# BrakeLightNM.net
KiCad netlist of a schematic drawn in Altium Designer
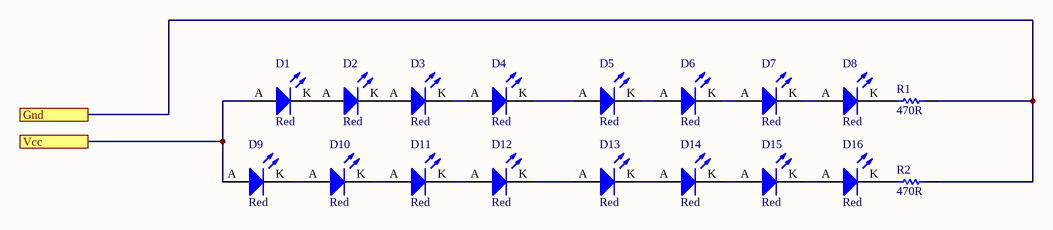
[diagram p0: BrakeLightNM.SchDoc]

(export (version "E")
  (design (tool "Eeschema 10.0.6"))
  (components
    (comp (ref "D1")
      (value "Red")
      (footprint "0805 LED")
      (description "Red LED Indication - Discrete 1.75V 0805 (2012 Metric)")
      (fields (field (name "PART NUMBER") "SML-210LTT86") (field (name "MANUFACTURER") "ROHM Semiconductor"))
      (libsource (lib "ts_20-standard-library") (part "LED"))
    )
    (comp (ref "D2")
      (value "Red")
      (footprint "0805 LED")
      (description "Red LED Indication - Discrete 1.75V 0805 (2012 Metric)")
      (fields (field (name "PART NUMBER") "SML-210LTT86") (field (name "MANUFACTURER") "ROHM Semiconductor"))
      (libsource (lib "ts_20-standard-library") (part "LED"))
    )
    (comp (ref "D3")
      (value "Red")
      (footprint "0805 LED")
      (description "Red LED Indication - Discrete 1.75V 0805 (2012 Metric)")
      (fields (field (name "PART NUMBER") "SML-210LTT86") (field (name "MANUFACTURER") "ROHM Semiconductor"))
      (libsource (lib "ts_20-standard-library") (part "LED"))
    )
    (comp (ref "D4")
      (value "Red")
      (footprint "0805 LED")
      (description "Red LED Indication - Discrete 1.75V 0805 (2012 Metric)")
      (fields (field (name "PART NUMBER") "SML-210LTT86") (field (name "MANUFACTURER") "ROHM Semiconductor"))
      (libsource (lib "ts_20-standard-library") (part "LED"))
    )
    (comp (ref "D5")
      (value "Red")
      (footprint "0805 LED")
      (description "Red LED Indication - Discrete 1.75V 0805 (2012 Metric)")
      (fields (field (name "PART NUMBER") "SML-210LTT86") (field (name "MANUFACTURER") "ROHM Semiconductor"))
      (libsource (lib "ts_20-standard-library") (part "LED"))
    )
    (comp (ref "D6")
      (value "Red")
      (footprint "0805 LED")
      (description "Red LED Indication - Discrete 1.75V 0805 (2012 Metric)")
      (fields (field (name "PART NUMBER") "SML-210LTT86") (field (name "MANUFACTURER") "ROHM Semiconductor"))
      (libsource (lib "ts_20-standard-library") (part "LED"))
    )
    (comp (ref "D7")
      (value "Red")
      (footprint "0805 LED")
      (description "Red LED Indication - Discrete 1.75V 0805 (2012 Metric)")
      (fields (field (name "PART NUMBER") "SML-210LTT86") (field (name "MANUFACTURER") "ROHM Semiconductor"))
      (libsource (lib "ts_20-standard-library") (part "LED"))
    )
    (comp (ref "D8")
      (value "Red")
      (footprint "0805 LED")
      (description "Red LED Indication - Discrete 1.75V 0805 (2012 Metric)")
      (fields (field (name "PART NUMBER") "SML-210LTT86") (field (name "MANUFACTURER") "ROHM Semiconductor"))
      (libsource (lib "ts_20-standard-library") (part "LED"))
    )
    (comp (ref "D9")
      (value "Red")
      (footprint "0805 LED")
      (description "Red LED Indication - Discrete 1.75V 0805 (2012 Metric)")
      (fields (field (name "PART NUMBER") "SML-210LTT86") (field (name "MANUFACTURER") "ROHM Semiconductor"))
      (libsource (lib "ts_20-standard-library") (part "LED"))
    )
    (comp (ref "D10")
      (value "Red")
      (footprint "0805 LED")
      (description "Red LED Indication - Discrete 1.75V 0805 (2012 Metric)")
      (fields (field (name "PART NUMBER") "SML-210LTT86") (field (name "MANUFACTURER") "ROHM Semiconductor"))
      (libsource (lib "ts_20-standard-library") (part "LED"))
    )
    (comp (ref "D11")
      (value "Red")
      (footprint "0805 LED")
      (description "Red LED Indication - Discrete 1.75V 0805 (2012 Metric)")
      (fields (field (name "PART NUMBER") "SML-210LTT86") (field (name "MANUFACTURER") "ROHM Semiconductor"))
      (libsource (lib "ts_20-standard-library") (part "LED"))
    )
    (comp (ref "D12")
      (value "Red")
      (footprint "0805 LED")
      (description "Red LED Indication - Discrete 1.75V 0805 (2012 Metric)")
      (fields (field (name "PART NUMBER") "SML-210LTT86") (field (name "MANUFACTURER") "ROHM Semiconductor"))
      (libsource (lib "ts_20-standard-library") (part "LED"))
    )
    (comp (ref "D13")
      (value "Red")
      (footprint "0805 LED")
      (description "Red LED Indication - Discrete 1.75V 0805 (2012 Metric)")
      (fields (field (name "PART NUMBER") "SML-210LTT86") (field (name "MANUFACTURER") "ROHM Semiconductor"))
      (libsource (lib "ts_20-standard-library") (part "LED"))
    )
    (comp (ref "D14")
      (value "Red")
      (footprint "0805 LED")
      (description "Red LED Indication - Discrete 1.75V 0805 (2012 Metric)")
      (fields (field (name "PART NUMBER") "SML-210LTT86") (field (name "MANUFACTURER") "ROHM Semiconductor"))
      (libsource (lib "ts_20-standard-library") (part "LED"))
    )
    (comp (ref "D15")
      (value "Red")
      (footprint "0805 LED")
      (description "Red LED Indication - Discrete 1.75V 0805 (2012 Metric)")
      (fields (field (name "PART NUMBER") "SML-210LTT86") (field (name "MANUFACTURER") "ROHM Semiconductor"))
      (libsource (lib "ts_20-standard-library") (part "LED"))
    )
    (comp (ref "D16")
      (value "Red")
      (footprint "0805 LED")
      (description "Red LED Indication - Discrete 1.75V 0805 (2012 Metric)")
      (fields (field (name "PART NUMBER") "SML-210LTT86") (field (name "MANUFACTURER") "ROHM Semiconductor"))
      (libsource (lib "ts_20-standard-library") (part "LED"))
    )
    (comp (ref "R1")
      (value "470R")
      (footprint "0805")
      (fields
        (field (name "PART NUMBER") "RC0805FR07470RL")
        (field (name "MANUFACTURER") "YAGEO")
        (field (name "TOLERANCE") "0.01")
      )
      (libsource (lib "ts_20-standard-library") (part "Resistor"))
    )
    (comp (ref "R2")
      (value "470R")
      (footprint "0805")
      (fields
        (field (name "PART NUMBER") "RC0805FR07470RL")
        (field (name "MANUFACTURER") "YAGEO")
        (field (name "TOLERANCE") "0.01")
      )
      (libsource (lib "ts_20-standard-library") (part "Resistor"))
    )
  )
  (nets
    (net (code "1") (name "/Gnd") (class "Default")
      (node (ref "R1") (pin "2") (pinfunction "2_2") (pintype "passive"))
      (node (ref "R2") (pin "2") (pinfunction "2_2") (pintype "passive"))
    )
    (net (code "2") (name "/Vcc") (class "Default")
      (node (ref "D1") (pin "A") (pinfunction "A_A") (pintype "passive"))
      (node (ref "D9") (pin "A") (pinfunction "A_A") (pintype "passive"))
    )
    (net (code "3") (name "Net-(D1-PadK)") (class "Default")
      (node (ref "D1") (pin "K") (pinfunction "K_K") (pintype "passive"))
      (node (ref "D2") (pin "A") (pinfunction "A_A") (pintype "passive"))
    )
    (net (code "4") (name "Net-(D2-PadK)") (class "Default")
      (node (ref "D2") (pin "K") (pinfunction "K_K") (pintype "passive"))
      (node (ref "D3") (pin "A") (pinfunction "A_A") (pintype "passive"))
    )
    (net (code "5") (name "Net-(D3-PadK)") (class "Default")
      (node (ref "D3") (pin "K") (pinfunction "K_K") (pintype "passive"))
      (node (ref "D4") (pin "A") (pinfunction "A_A") (pintype "passive"))
    )
    (net (code "6") (name "Net-(D4-PadK)") (class "Default")
      (node (ref "D4") (pin "K") (pinfunction "K_K") (pintype "passive"))
      (node (ref "D5") (pin "A") (pinfunction "A_A") (pintype "passive"))
    )
    (net (code "7") (name "Net-(D5-PadK)") (class "Default")
      (node (ref "D5") (pin "K") (pinfunction "K_K") (pintype "passive"))
      (node (ref "D6") (pin "A") (pinfunction "A_A") (pintype "passive"))
    )
    (net (code "8") (name "Net-(D6-PadK)") (class "Default")
      (node (ref "D6") (pin "K") (pinfunction "K_K") (pintype "passive"))
      (node (ref "D7") (pin "A") (pinfunction "A_A") (pintype "passive"))
    )
    (net (code "9") (name "Net-(D7-PadK)") (class "Default")
      (node (ref "D7") (pin "K") (pinfunction "K_K") (pintype "passive"))
      (node (ref "D8") (pin "A") (pinfunction "A_A") (pintype "passive"))
    )
    (net (code "10") (name "Net-(D8-PadK)") (class "Default")
      (node (ref "D8") (pin "K") (pinfunction "K_K") (pintype "passive"))
      (node (ref "R1") (pin "1") (pinfunction "1_1") (pintype "passive"))
    )
    (net (code "11") (name "Net-(D10-PadA)") (class "Default")
      (node (ref "D10") (pin "A") (pinfunction "A_A") (pintype "passive"))
      (node (ref "D9") (pin "K") (pinfunction "K_K") (pintype "passive"))
    )
    (net (code "12") (name "Net-(D10-PadK)") (class "Default")
      (node (ref "D10") (pin "K") (pinfunction "K_K") (pintype "passive"))
      (node (ref "D11") (pin "A") (pinfunction "A_A") (pintype "passive"))
    )
    (net (code "13") (name "Net-(D11-PadK)") (class "Default")
      (node (ref "D11") (pin "K") (pinfunction "K_K") (pintype "passive"))
      (node (ref "D12") (pin "A") (pinfunction "A_A") (pintype "passive"))
    )
    (net (code "14") (name "Net-(D12-PadK)") (class "Default")
      (node (ref "D12") (pin "K") (pinfunction "K_K") (pintype "passive"))
      (node (ref "D13") (pin "A") (pinfunction "A_A") (pintype "passive"))
    )
    (net (code "15") (name "Net-(D13-PadK)") (class "Default")
      (node (ref "D13") (pin "K") (pinfunction "K_K") (pintype "passive"))
      (node (ref "D14") (pin "A") (pinfunction "A_A") (pintype "passive"))
    )
    (net (code "16") (name "Net-(D14-PadK)") (class "Default")
      (node (ref "D14") (pin "K") (pinfunction "K_K") (pintype "passive"))
      (node (ref "D15") (pin "A") (pinfunction "A_A") (pintype "passive"))
    )
    (net (code "17") (name "Net-(D15-PadK)") (class "Default")
      (node (ref "D15") (pin "K") (pinfunction "K_K") (pintype "passive"))
      (node (ref "D16") (pin "A") (pinfunction "A_A") (pintype "passive"))
    )
    (net (code "18") (name "Net-(D16-PadK)") (class "Default")
      (node (ref "D16") (pin "K") (pinfunction "K_K") (pintype "passive"))
      (node (ref "R2") (pin "1") (pinfunction "1_1") (pintype "passive"))
    )
  )
)
